# AWSAM_5_Breakout.net
KiCad netlist of a schematic drawn in Altium Designer
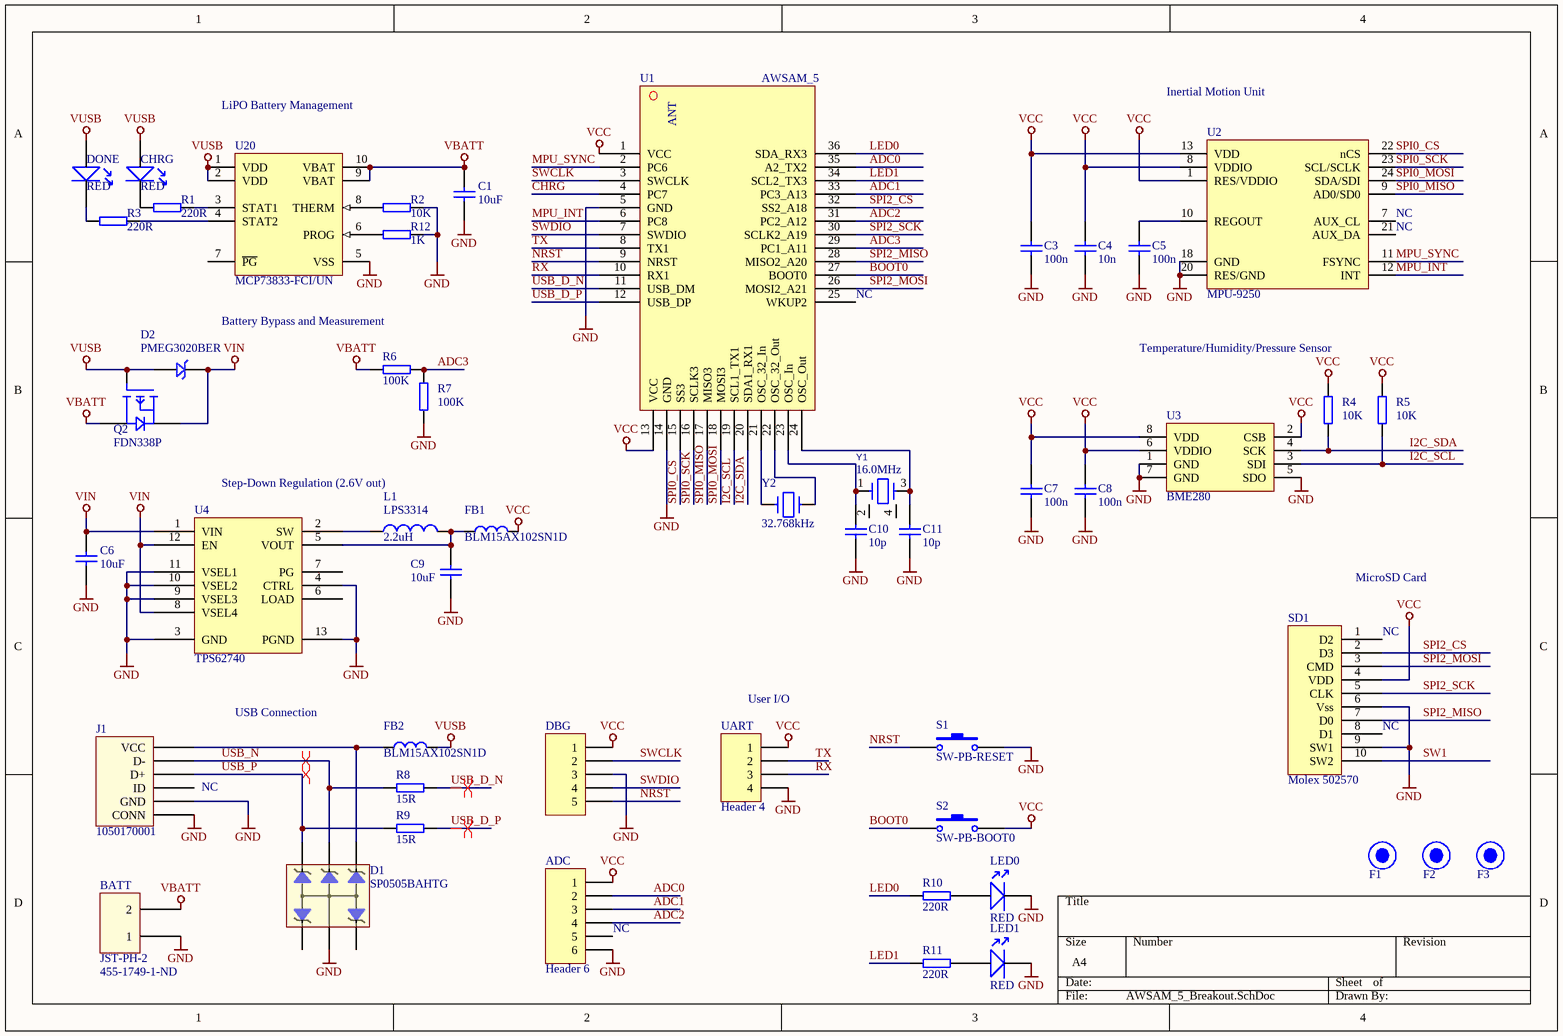
[diagram p0: AWSAM_5_Breakout.SchDoc]

(export (version "E")
  (design (tool "Eeschema 10.0.6"))
  (components
    (comp (ref "ADC")
      (value "Header 6")
      (footprint "HDR1X6")
      (description "Header, 6-Pin")
      (fields (field (name "PUBLISHER") "Altium Limited"))
      (libsource (lib "Miscellaneous Connectors") (part "Header 6"))
    )
    (comp (ref "BATT")
      (value "JST-PH-2")
      (footprint "JST-PH-2POS")
      (description "CONN SM JST PH 2-POS")
      (fields (field (name "SUPPLIER PART NUMBER 1") "455-1749-1-ND"))
      (libsource (lib "electronpowered") (part "S2B-PH-SM4-TB"))
    )
    (comp (ref "C1")
      (value "10uF")
      (footprint "CAP0603")
      (description "CAP SM 0603 X5R 10uF")
      (fields (field (name "PART NUMBER") "CAP-SM-0603-X5R-10uF") (field (name "MANUFACTURER") "GENERIC"))
      (libsource (lib "electronpowered") (part "CAP"))
    )
    (comp (ref "C3")
      (value "100n")
      (footprint "CAP0402")
      (description "CAP SM 0402 X7R 100NF")
      (fields (field (name "PART NUMBER") "CAP-SM-0402-X7R-100NF") (field (name "MANUFACTURER") "GENERIC"))
      (libsource (lib "electronpowered") (part "CAP"))
    )
    (comp (ref "C4")
      (value "10n")
      (footprint "CAP0402")
      (description "CAP SM 0402 X7R 10NF")
      (fields (field (name "PART NUMBER") "CAP-SM-0402-X7R-10NF") (field (name "MANUFACTURER") "GENERIC"))
      (libsource (lib "electronpowered") (part "CAP"))
    )
    (comp (ref "C5")
      (value "100n")
      (footprint "CAP0402")
      (description "CAP SM 0402 X7R 100NF")
      (fields (field (name "PART NUMBER") "CAP-SM-0402-X7R-100NF") (field (name "MANUFACTURER") "GENERIC"))
      (libsource (lib "electronpowered") (part "CAP"))
    )
    (comp (ref "C6")
      (value "10uF")
      (footprint "CAP0603")
      (description "CAP SM 0603 X5R 10uF")
      (fields (field (name "PART NUMBER") "CAP-SM-0603-X5R-10uF") (field (name "MANUFACTURER") "GENERIC"))
      (libsource (lib "electronpowered") (part "CAP"))
    )
    (comp (ref "C7")
      (value "100n")
      (footprint "CAP0402")
      (description "CAP SM 0402 X7R 100NF")
      (fields (field (name "PART NUMBER") "CAP-SM-0402-X7R-100NF") (field (name "MANUFACTURER") "GENERIC"))
      (libsource (lib "electronpowered") (part "CAP"))
    )
    (comp (ref "C8")
      (value "100n")
      (footprint "CAP0402")
      (description "CAP SM 0402 X7R 100NF")
      (fields (field (name "PART NUMBER") "CAP-SM-0402-X7R-100NF") (field (name "MANUFACTURER") "GENERIC"))
      (libsource (lib "electronpowered") (part "CAP"))
    )
    (comp (ref "C9")
      (value "10uF")
      (footprint "CAP0603")
      (description "CAP SM 0603 X5R 10uF")
      (fields (field (name "PART NUMBER") "CAP-SM-0603-X5R-10uF") (field (name "MANUFACTURER") "GENERIC"))
      (libsource (lib "electronpowered") (part "CAP"))
    )
    (comp (ref "C10")
      (value "10p")
      (footprint "CAP0402")
      (description "CAP SM 0402 NP0 10PF")
      (fields (field (name "PART NUMBER") "CAP-SM-0402-NP0-10PF") (field (name "MANUFACTURER") "GENERIC"))
      (libsource (lib "electronpowered") (part "CAP"))
    )
    (comp (ref "C11")
      (value "10p")
      (footprint "CAP0402")
      (description "CAP SM 0402 NP0 10PF")
      (fields (field (name "PART NUMBER") "CAP-SM-0402-NP0-10PF") (field (name "MANUFACTURER") "GENERIC"))
      (libsource (lib "electronpowered") (part "CAP"))
    )
    (comp (ref "CHRG")
      (value "RED")
      (footprint "SMT1206-LED")
      (description "LED SM 1206 RED 2V FWD VOLTAGE")
      (libsource (lib "electronpowered") (part "LTST-C150KRKT"))
    )
    (comp (ref "D1")
      (value "SP0505BAHTG")
      (footprint "SOT26A-6L")
      (description "IC DIODE TRANS VOLT SUPPR 5 PACKAGE")
      (fields (field (name "MANUFACTURER") "Little Fuse"))
      (libsource (lib "electronpowered") (part "SP0505BAHTG"))
    )
    (comp (ref "D2")
      (value "DIODE-SCHOTTKY")
      (footprint "DB2G42600L1")
      (description "DIODE  SCHOTTKY 1A 40V")
      (fields (field (name "PART NUMBER") "PMEG3020BER") (field (name "MANUFACTURER") "Panasonic"))
      (libsource (lib "electronpowered") (part "DIODE-SCHOTTKY"))
    )
    (comp (ref "DBG")
      (value "~")
      (footprint "HDR1X5")
      (description "Header, 5-Pin")
      (fields (field (name "PUBLISHER") "Altium Limited"))
      (libsource (lib "Miscellaneous Connectors") (part "Header 5"))
    )
    (comp (ref "DONE")
      (value "RED")
      (footprint "SMT1206-LED")
      (description "LED SM 1206 RED 2V FWD VOLTAGE")
      (libsource (lib "electronpowered") (part "LTST-C150KRKT"))
    )
    (comp (ref "F1")
      (value "FIDUCIAL")
      (footprint "FIDUCIAL-1MM")
      (description "FIDUCIAL 1MM CENTER")
      (fields (field (name "PART NUMBER") "FIDUCIAL-1MM"))
      (libsource (lib "electronpowered") (part "FIDUCIAL"))
    )
    (comp (ref "F2")
      (value "FIDUCIAL")
      (footprint "FIDUCIAL-1MM")
      (description "FIDUCIAL 1MM CENTER")
      (fields (field (name "PART NUMBER") "FIDUCIAL-1MM"))
      (libsource (lib "electronpowered") (part "FIDUCIAL"))
    )
    (comp (ref "F3")
      (value "FIDUCIAL")
      (footprint "FIDUCIAL-1MM")
      (description "FIDUCIAL 1MM CENTER")
      (fields (field (name "PART NUMBER") "FIDUCIAL-1MM"))
      (libsource (lib "electronpowered") (part "FIDUCIAL"))
    )
    (comp (ref "FB1")
      (value "IND")
      (footprint "IND0402")
      (description "FERRITE BEAD 350mA 0402")
      (fields (field (name "PART NUMBER") "BLM15AX102SN1D") (field (name "MANUFACTURER") "Murata"))
      (libsource (lib "electronpowered") (part "IND"))
    )
    (comp (ref "FB2")
      (value "IND")
      (footprint "IND0402")
      (description "FERRITE BEAD 350mA 0402")
      (fields (field (name "PART NUMBER") "BLM15AX102SN1D") (field (name "MANUFACTURER") "Murata"))
      (libsource (lib "electronpowered") (part "IND"))
    )
    (comp (ref "J1")
      (value "1050170001")
      (footprint "1050170001")
      (description "CONN RCPT MICRO USB R/A SMD")
      (fields (field (name "MANUFACTURER") "MOLEX"))
      (libsource (lib "electronpowered") (part "1050170001"))
    )
    (comp (ref "L1")
      (value "LPS3314")
      (footprint "CoilCraft- LPS3314")
      (description "Inductor")
      (fields (field (name "ALTIUM_VALUE") "2.2uH") (field (name "PUBLISHER") "Altium Limited"))
      (libsource (lib "Miscellaneous Devices") (part "Inductor"))
    )
    (comp (ref "LED0")
      (value "RED")
      (footprint "SMT1206-LED")
      (description "LED SM 1206 RED 2V FWD VOLTAGE")
      (libsource (lib "electronpowered") (part "LTST-C150KRKT"))
    )
    (comp (ref "LED1")
      (value "RED")
      (footprint "SMT1206-LED")
      (description "LED SM 1206 RED 2V FWD VOLTAGE")
      (libsource (lib "electronpowered") (part "LTST-C150KRKT"))
    )
    (comp (ref "Q2")
      (value "FET-PCH-DIODE")
      (footprint "SOT23-3")
      (description "MOSFET P-CH 20V 115MA SOT23-3")
      (fields (field (name "PART NUMBER") "FDN338P") (field (name "MANUFACTURER") "Fairchild"))
      (libsource (lib "electronpowered") (part "FET-PCH-DIODE"))
    )
    (comp (ref "R1")
      (value "220R")
      (footprint "SMT0402")
      (description "RES SM 0603 220R")
      (fields (field (name "Comment") "Resistor"))
      (libsource (lib "electronpowered") (part "RES-SM-0603-220R"))
    )
    (comp (ref "R2")
      (value "10K")
      (footprint "SMT0402")
      (description "RES SM 0402 10K")
      (fields (field (name "PART NUMBER") "RES-SM-0402-10K") (field (name "MANUFACTURER") "GENERIC"))
      (libsource (lib "electronpowered") (part "RES"))
    )
    (comp (ref "R3")
      (value "220R")
      (footprint "SMT0402")
      (description "RES SM 0603 220R")
      (fields (field (name "Comment") "Resistor"))
      (libsource (lib "electronpowered") (part "RES-SM-0603-220R"))
    )
    (comp (ref "R4")
      (value "10K")
      (footprint "SMT0402")
      (description "RES SM 0402 10K")
      (fields (field (name "PART NUMBER") "RES-SM-0402-10K") (field (name "MANUFACTURER") "GENERIC"))
      (libsource (lib "electronpowered") (part "RES"))
    )
    (comp (ref "R5")
      (value "10K")
      (footprint "SMT0402")
      (description "RES SM 0402 10K")
      (fields (field (name "PART NUMBER") "RES-SM-0402-10K") (field (name "MANUFACTURER") "GENERIC"))
      (libsource (lib "electronpowered") (part "RES"))
    )
    (comp (ref "R6")
      (value "100K")
      (footprint "SMT0402")
      (description "RES SM 0402 100K")
      (fields (field (name "PART NUMBER") "RES-SM-0402-100K") (field (name "MANUFACTURER") "GENERIC"))
      (libsource (lib "electronpowered") (part "RES"))
    )
    (comp (ref "R7")
      (value "100K")
      (footprint "SMT0402")
      (description "RES SM 0402 100K")
      (fields (field (name "PART NUMBER") "RES-SM-0402-100K") (field (name "MANUFACTURER") "GENERIC"))
      (libsource (lib "electronpowered") (part "RES"))
    )
    (comp (ref "R8")
      (value "15R")
      (footprint "SMT0402")
      (description "RES SM 0603 22K")
      (fields (field (name "Comment") "Resistor"))
      (libsource (lib "electronpowered") (part "RES-SM-0603-22K"))
    )
    (comp (ref "R9")
      (value "15R")
      (footprint "SMT0402")
      (description "RES SM 0603 22K")
      (fields (field (name "Comment") "Resistor"))
      (libsource (lib "electronpowered") (part "RES-SM-0603-22K"))
    )
    (comp (ref "R10")
      (value "220R")
      (footprint "SMT0402")
      (description "RES SM 0603 220R")
      (fields (field (name "Comment") "Resistor"))
      (libsource (lib "electronpowered") (part "RES-SM-0603-220R"))
    )
    (comp (ref "R11")
      (value "220R")
      (footprint "SMT0402")
      (description "RES SM 0603 220R")
      (fields (field (name "Comment") "Resistor"))
      (libsource (lib "electronpowered") (part "RES-SM-0603-220R"))
    )
    (comp (ref "R12")
      (value "1K")
      (footprint "SMT0402")
      (description "RES SM 0402 1K")
      (fields (field (name "PART NUMBER") "RES-SM-0402-1K") (field (name "MANUFACTURER") "GENERIC"))
      (libsource (lib "electronpowered") (part "RES"))
    )
    (comp (ref "S1")
      (value "SW-PB-RESET")
      (footprint "MC32882 Switch")
      (description "Switch")
      (fields (field (name "PUBLISHER") "Altium Limited"))
      (libsource (lib "Miscellaneous Devices") (part "SW-PB"))
    )
    (comp (ref "S2")
      (value "SW-PB-BOOT0")
      (footprint "MC32882 Switch")
      (description "Switch")
      (fields (field (name "PUBLISHER") "Altium Limited"))
      (libsource (lib "Miscellaneous Devices") (part "SW-PB"))
    )
    (comp (ref "SD1")
      (value "Molex 502570")
      (footprint "micro SD")
      (description "CONN SM MICROSD")
      (libsource (lib "AWSAM_5") (part "MOLEX-502570"))
    )
    (comp (ref "U1") (value "AWSAM_5") (footprint "AWSAM_5") (libsource (lib "AWSAM_5") (part "AWSAM_5")))
    (comp (ref "U2")
      (value "MPU-9250")
      (footprint "QFN24")
      (description "IC 9DOF IMU")
      (fields (field (name "MANUFACTURER") "InvenSense"))
      (libsource (lib "electronpowered") (part "MPU-9250"))
    )
    (comp (ref "U3")
      (value "BME280")
      (footprint "BME280")
      (description "IC SENSOR PRESS/HUMID/TEMP")
      (fields (field (name "MANUFACTURER") "Bosch"))
      (libsource (lib "electronpowered") (part "BME280"))
    )
    (comp (ref "U4")
      (value "TPS62740")
      (footprint "TPS62740_12Pin")
      (description "IC REG BUCK")
      (fields (field (name "MANUFACTURER") "Texas Instruments"))
      (libsource (lib "electronpowered") (part "TPS62740"))
    )
    (comp (ref "U20")
      (value "MCP73833-FCI/UN")
      (footprint "MSOP-UN10_N")
      (fields (field (name "PUBLISHER") "Altium Limited"))
      (libsource (lib "Microchip Power Mgt Battery Management") (part "MCP73833-FCI/UN"))
    )
    (comp (ref "UART")
      (value "Header 4")
      (footprint "HDR1X4")
      (description "Header, 4-Pin")
      (fields (field (name "PUBLISHER") "Altium Limited"))
      (libsource (lib "Miscellaneous Connectors") (part "Header 4"))
    )
    (comp (ref "Y1")
      (value "16.0MHz")
      (footprint "AP7-00061")
      (description "16MHz uXtal, 3.2 x 2.5 mm SMD, CL=9pF, 15PPM, ESR=80ohm(Max.")
      (fields (field (name "TOLERANCE") "15ppm") (field (name "MANUFACTURER") "Epson Toyocom"))
      (libsource (lib "AltiumDbLib") (part "TSX-3225"))
    )
    (comp (ref "Y2")
      (value "CM315-32.768KEZF-UT")
      (footprint "SMD Crystal 32kHz")
      (description "CRYSTAL 32.768KHZ 12.5PF SMD")
      (fields (field (name "MANUFACTURER") "Citizen Finetech Miyota") (field (name "FREQUENCY") "32.768kHz"))
      (libsource (lib "AWSAM_5") (part "CM315-32.768KEZF-UT"))
    )
  )
  (nets
    (net (code "1") (name "/ADC0") (class "Default")
      (node (ref "ADC") (pin "2") (pinfunction "2_2") (pintype "passive"))
      (node (ref "U1") (pin "35") (pinfunction "A2_TX2_35") (pintype "passive"))
    )
    (net (code "2") (name "/ADC1") (class "Default")
      (node (ref "ADC") (pin "3") (pinfunction "3_3") (pintype "passive"))
      (node (ref "U1") (pin "33") (pinfunction "PC3_A13_33") (pintype "passive"))
    )
    (net (code "3") (name "/ADC2") (class "Default")
      (node (ref "ADC") (pin "4") (pinfunction "4_4") (pintype "passive"))
      (node (ref "U1") (pin "31") (pinfunction "PC2_A12_31") (pintype "passive"))
    )
    (net (code "4") (name "/ADC3") (class "Default")
      (node (ref "R6") (pin "1") (pinfunction "1_1") (pintype "passive"))
      (node (ref "R7") (pin "2") (pinfunction "2_2") (pintype "passive"))
      (node (ref "U1") (pin "29") (pinfunction "PC1_A11_29") (pintype "passive"))
    )
    (net (code "5") (name "/BOOT0") (class "Default")
      (node (ref "S2") (pin "1") (pinfunction "1_1") (pintype "passive"))
      (node (ref "U1") (pin "27") (pinfunction "BOOT0_27") (pintype "passive"))
    )
    (net (code "6") (name "/CHRG") (class "Default")
      (node (ref "U1") (pin "4") (pinfunction "PC7_4") (pintype "passive"))
    )
    (net (code "7") (name "/I2C_SCL") (class "Default")
      (node (ref "R5") (pin "1") (pinfunction "1_1") (pintype "passive"))
      (node (ref "U1") (pin "19") (pinfunction "SCL1_TX1_19") (pintype "passive"))
      (node (ref "U3") (pin "3") (pinfunction "SDI_3") (pintype "passive"))
    )
    (net (code "8") (name "/I2C_SDA") (class "Default")
      (node (ref "R4") (pin "1") (pinfunction "1_1") (pintype "passive"))
      (node (ref "U1") (pin "20") (pinfunction "SDA1_RX1_20") (pintype "passive"))
      (node (ref "U3") (pin "4") (pinfunction "SCK_4") (pintype "passive"))
    )
    (net (code "9") (name "/LED0") (class "Default")
      (node (ref "R10") (pin "2") (pinfunction "2_2") (pintype "passive"))
      (node (ref "U1") (pin "36") (pinfunction "SDA_RX3_36") (pintype "passive"))
    )
    (net (code "10") (name "/LED1") (class "Default")
      (node (ref "R11") (pin "2") (pinfunction "2_2") (pintype "passive"))
      (node (ref "U1") (pin "34") (pinfunction "SCL2_TX3_34") (pintype "passive"))
    )
    (net (code "11") (name "/MPU_INT") (class "Default")
      (node (ref "U1") (pin "6") (pinfunction "PC8_6") (pintype "passive"))
      (node (ref "U2") (pin "12") (pinfunction "INT_12") (pintype "passive"))
    )
    (net (code "12") (name "/MPU_SYNC") (class "Default")
      (node (ref "U1") (pin "2") (pinfunction "PC6_2") (pintype "passive"))
      (node (ref "U2") (pin "11") (pinfunction "FSYNC_11") (pintype "passive"))
    )
    (net (code "13") (name "/NRST") (class "Default")
      (node (ref "DBG") (pin "5") (pinfunction "5_5") (pintype "passive"))
      (node (ref "S1") (pin "1") (pinfunction "1_1") (pintype "passive"))
      (node (ref "U1") (pin "9") (pinfunction "NRST_9") (pintype "passive"))
    )
    (net (code "14") (name "/RX") (class "Default")
      (node (ref "U1") (pin "10") (pinfunction "RX1_10") (pintype "passive"))
      (node (ref "UART") (pin "3") (pinfunction "3_3") (pintype "passive"))
    )
    (net (code "15") (name "/SPI0_CS") (class "Default")
      (node (ref "U1") (pin "15") (pinfunction "SS3_15") (pintype "passive"))
      (node (ref "U2") (pin "22") (pinfunction "nCS_22") (pintype "passive"))
    )
    (net (code "16") (name "/SPI0_MISO") (class "Default")
      (node (ref "U1") (pin "17") (pinfunction "MISO3_17") (pintype "passive"))
      (node (ref "U2") (pin "9") (pinfunction "AD0/SD0_9") (pintype "passive"))
    )
    (net (code "17") (name "/SPI0_MOSI") (class "Default")
      (node (ref "U1") (pin "18") (pinfunction "MOSI3_18") (pintype "passive"))
      (node (ref "U2") (pin "24") (pinfunction "SDA/SDI_24") (pintype "passive"))
    )
    (net (code "18") (name "/SPI0_SCK") (class "Default")
      (node (ref "U1") (pin "16") (pinfunction "SCLK3_16") (pintype "passive"))
      (node (ref "U2") (pin "23") (pinfunction "SCL/SCLK_23") (pintype "passive"))
    )
    (net (code "19") (name "/SPI2_CS") (class "Default")
      (node (ref "SD1") (pin "2") (pinfunction "D3_2") (pintype "passive"))
      (node (ref "U1") (pin "32") (pinfunction "SS2_A18_32") (pintype "passive"))
    )
    (net (code "20") (name "/SPI2_MISO") (class "Default")
      (node (ref "SD1") (pin "7") (pinfunction "D0_7") (pintype "passive"))
      (node (ref "U1") (pin "28") (pinfunction "MISO2_A20_28") (pintype "passive"))
    )
    (net (code "21") (name "/SPI2_MOSI") (class "Default")
      (node (ref "SD1") (pin "3") (pinfunction "CMD_3") (pintype "passive"))
      (node (ref "U1") (pin "26") (pinfunction "MOSI2_A21_26") (pintype "passive"))
    )
    (net (code "22") (name "/SPI2_SCK") (class "Default")
      (node (ref "SD1") (pin "5") (pinfunction "CLK_5") (pintype "passive"))
      (node (ref "U1") (pin "30") (pinfunction "SCLK2_A19_30") (pintype "passive"))
    )
    (net (code "23") (name "/SW1") (class "Default")
      (node (ref "SD1") (pin "10") (pinfunction "SW2_10") (pintype "passive"))
    )
    (net (code "24") (name "/SWCLK") (class "Default")
      (node (ref "DBG") (pin "2") (pinfunction "2_2") (pintype "passive"))
      (node (ref "U1") (pin "3") (pinfunction "SWCLK_3") (pintype "passive"))
    )
    (net (code "25") (name "/SWDIO") (class "Default")
      (node (ref "DBG") (pin "4") (pinfunction "4_4") (pintype "passive"))
      (node (ref "U1") (pin "7") (pinfunction "SWDIO_7") (pintype "passive"))
    )
    (net (code "26") (name "/TX") (class "Default")
      (node (ref "U1") (pin "8") (pinfunction "TX1_8") (pintype "passive"))
      (node (ref "UART") (pin "2") (pinfunction "2_2") (pintype "passive"))
    )
    (net (code "27") (name "/USB_D_N") (class "Default")
      (node (ref "R8") (pin "1") (pinfunction "1_1") (pintype "passive"))
      (node (ref "U1") (pin "11") (pinfunction "USB_DM_11") (pintype "passive"))
    )
    (net (code "28") (name "/USB_D_P") (class "Default")
      (node (ref "R9") (pin "1") (pinfunction "1_1") (pintype "passive"))
      (node (ref "U1") (pin "12") (pinfunction "USB_DP_12") (pintype "passive"))
    )
    (net (code "29") (name "/USB_N") (class "Default")
      (node (ref "D1") (pin "5") (pinfunction "5_5") (pintype "passive"))
      (node (ref "J1") (pin "2") (pinfunction "D-_2") (pintype "passive"))
      (node (ref "R8") (pin "2") (pinfunction "2_2") (pintype "passive"))
    )
    (net (code "30") (name "/USB_P") (class "Default")
      (node (ref "D1") (pin "6") (pinfunction "6_6") (pintype "passive"))
      (node (ref "J1") (pin "3") (pinfunction "D+_3") (pintype "passive"))
      (node (ref "R9") (pin "2") (pinfunction "2_2") (pintype "passive"))
    )
    (net (code "31") (name "GND") (class "Default")
      (node (ref "ADC") (pin "6") (pinfunction "6_6") (pintype "passive"))
      (node (ref "BATT") (pin "1") (pinfunction "1_1") (pintype "passive"))
      (node (ref "C1") (pin "1") (pinfunction "1_1") (pintype "passive"))
      (node (ref "C10") (pin "1") (pinfunction "1_1") (pintype "passive"))
      (node (ref "C11") (pin "1") (pinfunction "1_1") (pintype "passive"))
      (node (ref "C3") (pin "1") (pinfunction "1_1") (pintype "passive"))
      (node (ref "C4") (pin "1") (pinfunction "1_1") (pintype "passive"))
      (node (ref "C5") (pin "1") (pinfunction "1_1") (pintype "passive"))
      (node (ref "C6") (pin "1") (pinfunction "1_1") (pintype "passive"))
      (node (ref "C7") (pin "1") (pinfunction "1_1") (pintype "passive"))
      (node (ref "C8") (pin "1") (pinfunction "1_1") (pintype "passive"))
      (node (ref "C9") (pin "1") (pinfunction "1_1") (pintype "passive"))
      (node (ref "D1") (pin "2") (pinfunction "2_2") (pintype "passive"))
      (node (ref "DBG") (pin "3") (pinfunction "3_3") (pintype "passive"))
      (node (ref "J1") (pin "0") (pinfunction "CONN_0") (pintype "passive"))
      (node (ref "J1") (pin "5") (pinfunction "GND_5") (pintype "passive"))
      (node (ref "LED0") (pin "2") (pinfunction "2_2") (pintype "passive"))
      (node (ref "LED1") (pin "2") (pinfunction "2_2") (pintype "passive"))
      (node (ref "R12") (pin "2") (pinfunction "2_2") (pintype "passive"))
      (node (ref "R2") (pin "2") (pinfunction "2_2") (pintype "passive"))
      (node (ref "R7") (pin "1") (pinfunction "1_1") (pintype "passive"))
      (node (ref "S1") (pin "2") (pinfunction "2_2") (pintype "passive"))
      (node (ref "SD1") (pin "6") (pinfunction "Vss_6") (pintype "passive"))
      (node (ref "SD1") (pin "9") (pinfunction "SW1_9") (pintype "passive"))
      (node (ref "U1") (pin "14") (pinfunction "GND_14") (pintype "passive"))
      (node (ref "U1") (pin "5") (pinfunction "GND_5") (pintype "passive"))
      (node (ref "U2") (pin "18") (pinfunction "GND_18") (pintype "passive"))
      (node (ref "U2") (pin "20") (pinfunction "RES/GND_20") (pintype "passive"))
      (node (ref "U20") (pin "5") (pinfunction "VSS_5") (pintype "power_in"))
      (node (ref "U3") (pin "1") (pinfunction "GND_1") (pintype "passive"))
      (node (ref "U3") (pin "5") (pinfunction "SDO_5") (pintype "passive"))
      (node (ref "U3") (pin "7") (pinfunction "GND_7") (pintype "passive"))
      (node (ref "U4") (pin "10") (pinfunction "VSEL2_10") (pintype "passive"))
      (node (ref "U4") (pin "11") (pinfunction "VSEL1_11") (pintype "passive"))
      (node (ref "U4") (pin "13") (pinfunction "PGND_13") (pintype "passive"))
      (node (ref "U4") (pin "3") (pinfunction "GND_3") (pintype "passive"))
      (node (ref "U4") (pin "4") (pinfunction "CTRL_4") (pintype "passive"))
      (node (ref "U4") (pin "9") (pinfunction "VSEL3_9") (pintype "passive"))
      (node (ref "UART") (pin "4") (pinfunction "4_4") (pintype "passive"))
    )
    (net (code "32") (name "Net-(CHRG-Pad2)") (class "Default")
      (node (ref "CHRG") (pin "2") (pinfunction "2_2") (pintype "passive"))
      (node (ref "R1") (pin "2") (pinfunction "2_2") (pintype "passive"))
    )
    (net (code "33") (name "Net-(DONE-Pad2)") (class "Default")
      (node (ref "DONE") (pin "2") (pinfunction "2_2") (pintype "passive"))
      (node (ref "R3") (pin "2") (pinfunction "2_2") (pintype "passive"))
    )
    (net (code "34") (name "Net-(J1-VCC)") (class "Default")
      (node (ref "D1") (pin "4") (pinfunction "4_4") (pintype "passive"))
      (node (ref "FB2") (pin "1") (pinfunction "1_1") (pintype "passive"))
      (node (ref "J1") (pin "1") (pinfunction "VCC_1") (pintype "passive"))
    )
    (net (code "35") (name "Net-(LED0-Pad1)") (class "Default")
      (node (ref "LED0") (pin "1") (pinfunction "1_1") (pintype "passive"))
      (node (ref "R10") (pin "1") (pinfunction "1_1") (pintype "passive"))
    )
    (net (code "36") (name "Net-(LED1-Pad1)") (class "Default")
      (node (ref "LED1") (pin "1") (pinfunction "1_1") (pintype "passive"))
      (node (ref "R11") (pin "1") (pinfunction "1_1") (pintype "passive"))
    )
    (net (code "37") (name "Net-(U1-OSC_32_In)") (class "Default")
      (node (ref "U1") (pin "21") (pinfunction "OSC_32_In_21") (pintype "passive"))
      (node (ref "Y2") (pin "1") (pinfunction "IN_1") (pintype "passive"))
    )
    (net (code "38") (name "Net-(U1-OSC_32_Out)") (class "Default")
      (node (ref "U1") (pin "22") (pinfunction "OSC_32_Out_22") (pintype "passive"))
      (node (ref "Y2") (pin "2") (pinfunction "OUT_2") (pintype "passive"))
    )
    (net (code "39") (name "Net-(U1-OSC_In)") (class "Default")
      (node (ref "C10") (pin "2") (pinfunction "2_2") (pintype "passive"))
      (node (ref "U1") (pin "23") (pinfunction "OSC_In_23") (pintype "passive"))
      (node (ref "Y1") (pin "1") (pinfunction "IN_1") (pintype "passive"))
    )
    (net (code "40") (name "Net-(U1-OSC_Out)") (class "Default")
      (node (ref "C11") (pin "2") (pinfunction "2_2") (pintype "passive"))
      (node (ref "U1") (pin "24") (pinfunction "OSC_Out_24") (pintype "passive"))
      (node (ref "Y1") (pin "3") (pinfunction "OUT_3") (pintype "passive"))
    )
    (net (code "41") (name "Net-(U2-REGOUT)") (class "Default")
      (node (ref "C5") (pin "2") (pinfunction "2_2") (pintype "passive"))
      (node (ref "U2") (pin "10") (pinfunction "REGOUT_10") (pintype "passive"))
    )
    (net (code "42") (name "Net-(U4-SW)") (class "Default")
      (node (ref "L1") (pin "1") (pinfunction "1_1") (pintype "passive"))
      (node (ref "U4") (pin "2") (pinfunction "SW_2") (pintype "passive"))
    )
    (net (code "43") (name "Net-(U4-VOUT)") (class "Default")
      (node (ref "C9") (pin "2") (pinfunction "2_2") (pintype "passive"))
      (node (ref "FB1") (pin "1") (pinfunction "1_1") (pintype "passive"))
      (node (ref "L1") (pin "2") (pinfunction "2_2") (pintype "passive"))
      (node (ref "U4") (pin "5") (pinfunction "VOUT_5") (pintype "passive"))
    )
    (net (code "44") (name "Net-(U20-PROG)") (class "Default")
      (node (ref "R12") (pin "1") (pinfunction "1_1") (pintype "passive"))
      (node (ref "U20") (pin "6") (pinfunction "PROG_6") (pintype "input"))
    )
    (net (code "45") (name "Net-(U20-STAT1)") (class "Default")
      (node (ref "R1") (pin "1") (pinfunction "1_1") (pintype "passive"))
      (node (ref "U20") (pin "3") (pinfunction "STAT1_3") (pintype "open_collector"))
    )
    (net (code "46") (name "Net-(U20-STAT2)") (class "Default")
      (node (ref "R3") (pin "1") (pinfunction "1_1") (pintype "passive"))
      (node (ref "U20") (pin "4") (pinfunction "STAT2_4") (pintype "open_collector"))
    )
    (net (code "47") (name "Net-(U20-THERM)") (class "Default")
      (node (ref "R2") (pin "1") (pinfunction "1_1") (pintype "passive"))
      (node (ref "U20") (pin "8") (pinfunction "THERM_8") (pintype "input"))
    )
    (net (code "48") (name "VBATT") (class "Default")
      (node (ref "BATT") (pin "2") (pinfunction "2_2") (pintype "passive"))
      (node (ref "C1") (pin "2") (pinfunction "2_2") (pintype "passive"))
      (node (ref "Q2") (pin "3") (pinfunction "3_3") (pintype "passive"))
      (node (ref "R6") (pin "2") (pinfunction "2_2") (pintype "passive"))
      (node (ref "U20") (pin "10") (pinfunction "VBAT_10") (pintype "power_in"))
      (node (ref "U20") (pin "9") (pinfunction "VBAT_9") (pintype "power_in"))
    )
    (net (code "49") (name "VCC") (class "Default")
      (node (ref "ADC") (pin "1") (pinfunction "1_1") (pintype "passive"))
      (node (ref "C3") (pin "2") (pinfunction "2_2") (pintype "passive"))
      (node (ref "C4") (pin "2") (pinfunction "2_2") (pintype "passive"))
      (node (ref "C7") (pin "2") (pinfunction "2_2") (pintype "passive"))
      (node (ref "C8") (pin "2") (pinfunction "2_2") (pintype "passive"))
      (node (ref "DBG") (pin "1") (pinfunction "1_1") (pintype "passive"))
      (node (ref "FB1") (pin "2") (pinfunction "2_2") (pintype "passive"))
      (node (ref "R4") (pin "2") (pinfunction "2_2") (pintype "passive"))
      (node (ref "R5") (pin "2") (pinfunction "2_2") (pintype "passive"))
      (node (ref "S2") (pin "2") (pinfunction "2_2") (pintype "passive"))
      (node (ref "SD1") (pin "4") (pinfunction "VDD_4") (pintype "passive"))
      (node (ref "U1") (pin "1") (pinfunction "VCC_1") (pintype "passive"))
      (node (ref "U1") (pin "13") (pinfunction "VCC_13") (pintype "passive"))
      (node (ref "U2") (pin "1") (pinfunction "RES/VDDIO_1") (pintype "passive"))
      (node (ref "U2") (pin "13") (pinfunction "VDD_13") (pintype "passive"))
      (node (ref "U2") (pin "8") (pinfunction "VDDIO_8") (pintype "passive"))
      (node (ref "U3") (pin "2") (pinfunction "CSB_2") (pintype "passive"))
      (node (ref "U3") (pin "6") (pinfunction "VDDIO_6") (pintype "passive"))
      (node (ref "U3") (pin "8") (pinfunction "VDD_8") (pintype "passive"))
      (node (ref "UART") (pin "1") (pinfunction "1_1") (pintype "passive"))
    )
    (net (code "50") (name "VIN") (class "Default")
      (node (ref "C6") (pin "2") (pinfunction "2_2") (pintype "passive"))
      (node (ref "D2") (pin "1") (pinfunction "1_1") (pintype "passive"))
      (node (ref "Q2") (pin "2") (pinfunction "2_2") (pintype "passive"))
      (node (ref "U4") (pin "1") (pinfunction "VIN_1") (pintype "passive"))
      (node (ref "U4") (pin "12") (pinfunction "EN_12") (pintype "passive"))
      (node (ref "U4") (pin "8") (pinfunction "VSEL4_8") (pintype "passive"))
    )
    (net (code "51") (name "VUSB") (class "Default")
      (node (ref "CHRG") (pin "1") (pinfunction "1_1") (pintype "passive"))
      (node (ref "D2") (pin "2") (pinfunction "2_2") (pintype "passive"))
      (node (ref "DONE") (pin "1") (pinfunction "1_1") (pintype "passive"))
      (node (ref "FB2") (pin "2") (pinfunction "2_2") (pintype "passive"))
      (node (ref "Q2") (pin "1") (pinfunction "1_1") (pintype "passive"))
      (node (ref "U20") (pin "1") (pinfunction "VDD_1") (pintype "power_in"))
      (node (ref "U20") (pin "2") (pinfunction "VDD_2") (pintype "power_in"))
    )
    (net (code "52") (name "unconnected-(ADC-Pad5)") (class "Default")
      (node (ref "ADC") (pin "5") (pinfunction "5_5") (pintype "passive"))
    )
    (net (code "53") (name "unconnected-(D1-Pad1)") (class "Default")
      (node (ref "D1") (pin "1") (pinfunction "1_1") (pintype "passive"))
    )
    (net (code "54") (name "unconnected-(D1-Pad3)") (class "Default")
      (node (ref "D1") (pin "3") (pinfunction "3_3") (pintype "passive"))
    )
    (net (code "55") (name "unconnected-(J1-ID-Pad4)") (class "Default")
      (node (ref "J1") (pin "4") (pinfunction "ID_4") (pintype "passive"))
    )
    (net (code "56") (name "unconnected-(SD1-D1-Pad8)") (class "Default")
      (node (ref "SD1") (pin "8") (pinfunction "D1_8") (pintype "passive"))
    )
    (net (code "57") (name "unconnected-(SD1-D2-Pad1)") (class "Default")
      (node (ref "SD1") (pin "1") (pinfunction "D2_1") (pintype "passive"))
    )
    (net (code "58") (name "unconnected-(U1-WKUP2-Pad25)") (class "Default")
      (node (ref "U1") (pin "25") (pinfunction "WKUP2_25") (pintype "passive"))
    )
    (net (code "59") (name "unconnected-(U2-AUX_CL-Pad7)") (class "Default")
      (node (ref "U2") (pin "7") (pinfunction "AUX_CL_7") (pintype "passive"))
    )
    (net (code "60") (name "unconnected-(U2-AUX_DA-Pad21)") (class "Default")
      (node (ref "U2") (pin "21") (pinfunction "AUX_DA_21") (pintype "passive"))
    )
    (net (code "61") (name "unconnected-(U4-LOAD-Pad6)") (class "Default")
      (node (ref "U4") (pin "6") (pinfunction "LOAD_6") (pintype "passive"))
    )
    (net (code "62") (name "unconnected-(U4-PG-Pad7)") (class "Default")
      (node (ref "U4") (pin "7") (pinfunction "PG_7") (pintype "passive"))
    )
    (net (code "63") (name "unconnected-(U20-~{PG}-Pad7)") (class "Default")
      (node (ref "U20") (pin "7") (pinfunction "~{PG}_7") (pintype "open_collector"))
    )
    (net (code "64") (name "unconnected-(Y1-GND-Pad2)") (class "Default")
      (node (ref "Y1") (pin "2") (pinfunction "GND_2") (pintype "passive"))
    )
    (net (code "65") (name "unconnected-(Y1-GND-Pad4)") (class "Default")
      (node (ref "Y1") (pin "4") (pinfunction "GND_4") (pintype "passive"))
    )
  )
)
